# ir.net
KiCad netlist of a schematic drawn in EAGLE
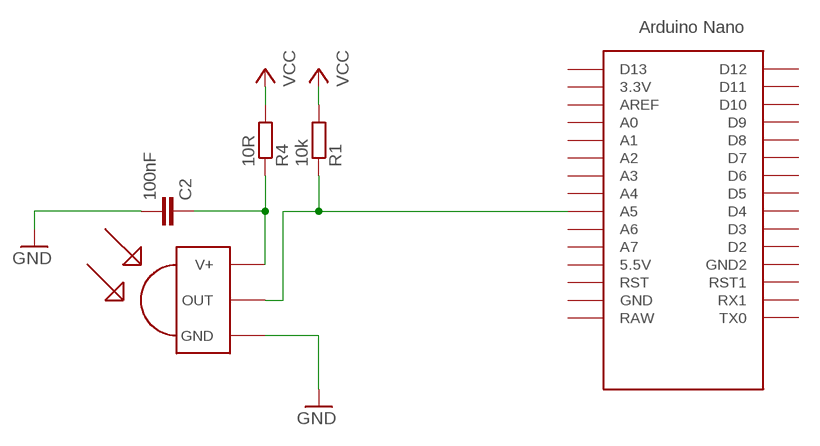
[diagram p0: schematic, sheet 1]

(export (version "E")
  (design (tool "Eeschema 10.0.6"))
  (components
    (comp (ref "C2")
      (value "100nF")
      (footprint "eagle-import:C025-025X050")
      (libsource (lib "eagle-import") (part "C-EU025-025X050"))
    )
    (comp (ref "R1")
      (value "10k")
      (footprint "eagle-import:0207_10")
      (libsource (lib "eagle-import") (part "R-EU_0207/10"))
    )
    (comp (ref "R4")
      (value "10R")
      (footprint "eagle-import:0207_10")
      (libsource (lib "eagle-import") (part "R-EU_0207/10"))
    )
    (comp (ref "U$1")
      (value "TSOP4838")
      (footprint "eagle-import:TSOP18XX")
      (libsource (lib "eagle-import") (part "TSOP4838"))
    )
    (comp (ref "U$2")
      (value "NANO")
      (footprint "eagle-import:NANO")
      (libsource (lib "eagle-import") (part "NANO"))
    )
  )
  (nets
    (net (code "1") (name "GND") (class "Default")
      (node (ref "C2") (pin "2") (pinfunction "2_2") (pintype "passive"))
      (node (ref "U$1") (pin "GND") (pinfunction "GND_GND") (pintype "bidirectional"))
    )
    (net (code "2") (name "Net-(R1-Pad1)") (class "Default")
      (node (ref "R1") (pin "1") (pinfunction "1_1") (pintype "passive"))
      (node (ref "U$1") (pin "OUT") (pinfunction "OUT_OUT") (pintype "bidirectional"))
      (node (ref "U$2") (pin "A5") (pinfunction "A5_A5") (pintype "bidirectional"))
    )
    (net (code "3") (name "Net-(U$1-V+)") (class "Default")
      (node (ref "C2") (pin "1") (pinfunction "1_1") (pintype "passive"))
      (node (ref "R4") (pin "1") (pinfunction "1_1") (pintype "passive"))
      (node (ref "U$1") (pin "VCC") (pinfunction "V+_VCC") (pintype "bidirectional"))
    )
    (net (code "4") (name "VCC") (class "Default")
      (node (ref "R1") (pin "2") (pinfunction "2_2") (pintype "passive"))
      (node (ref "R4") (pin "2") (pinfunction "2_2") (pintype "passive"))
    )
    (net (code "5") (name "unconnected-(U$2-5.5V-Pad5V)") (class "Default")
      (node (ref "U$2") (pin "5V") (pinfunction "5.5V_5V") (pintype "bidirectional"))
    )
    (net (code "6") (name "unconnected-(U$2-GND2-PadGND1)") (class "Default")
      (node (ref "U$2") (pin "GND1") (pinfunction "GND2_GND1") (pintype "bidirectional"))
    )
    (net (code "7") (name "unconnected-(U$2-Pad3.3V)") (class "Default")
      (node (ref "U$2") (pin "3.3V") (pinfunction "3.3V_3.3V") (pintype "bidirectional"))
    )
    (net (code "8") (name "unconnected-(U$2-PadA0)") (class "Default")
      (node (ref "U$2") (pin "A0") (pinfunction "A0_A0") (pintype "bidirectional"))
    )
    (net (code "9") (name "unconnected-(U$2-PadA1)") (class "Default")
      (node (ref "U$2") (pin "A1") (pinfunction "A1_A1") (pintype "bidirectional"))
    )
    (net (code "10") (name "unconnected-(U$2-PadA2)") (class "Default")
      (node (ref "U$2") (pin "A2") (pinfunction "A2_A2") (pintype "bidirectional"))
    )
    (net (code "11") (name "unconnected-(U$2-PadA3)") (class "Default")
      (node (ref "U$2") (pin "A3") (pinfunction "A3_A3") (pintype "bidirectional"))
    )
    (net (code "12") (name "unconnected-(U$2-PadA4)") (class "Default")
      (node (ref "U$2") (pin "A4") (pinfunction "A4_A4") (pintype "bidirectional"))
    )
    (net (code "13") (name "unconnected-(U$2-PadA6)") (class "Default")
      (node (ref "U$2") (pin "A6") (pinfunction "A6_A6") (pintype "bidirectional"))
    )
    (net (code "14") (name "unconnected-(U$2-PadA7)") (class "Default")
      (node (ref "U$2") (pin "A7") (pinfunction "A7_A7") (pintype "bidirectional"))
    )
    (net (code "15") (name "unconnected-(U$2-PadAREF)") (class "Default")
      (node (ref "U$2") (pin "AREF") (pinfunction "AREF_AREF") (pintype "bidirectional"))
    )
    (net (code "16") (name "unconnected-(U$2-PadD2)") (class "Default")
      (node (ref "U$2") (pin "D2") (pinfunction "D2_D2") (pintype "bidirectional"))
    )
    (net (code "17") (name "unconnected-(U$2-PadD3)") (class "Default")
      (node (ref "U$2") (pin "D3") (pinfunction "D3_D3") (pintype "bidirectional"))
    )
    (net (code "18") (name "unconnected-(U$2-PadD4)") (class "Default")
      (node (ref "U$2") (pin "D4") (pinfunction "D4_D4") (pintype "bidirectional"))
    )
    (net (code "19") (name "unconnected-(U$2-PadD5)") (class "Default")
      (node (ref "U$2") (pin "D5") (pinfunction "D5_D5") (pintype "bidirectional"))
    )
    (net (code "20") (name "unconnected-(U$2-PadD6)") (class "Default")
      (node (ref "U$2") (pin "D6") (pinfunction "D6_D6") (pintype "bidirectional"))
    )
    (net (code "21") (name "unconnected-(U$2-PadD7)") (class "Default")
      (node (ref "U$2") (pin "D7") (pinfunction "D7_D7") (pintype "bidirectional"))
    )
    (net (code "22") (name "unconnected-(U$2-PadD8)") (class "Default")
      (node (ref "U$2") (pin "D8") (pinfunction "D8_D8") (pintype "bidirectional"))
    )
    (net (code "23") (name "unconnected-(U$2-PadD9)") (class "Default")
      (node (ref "U$2") (pin "D9") (pinfunction "D9_D9") (pintype "bidirectional"))
    )
    (net (code "24") (name "unconnected-(U$2-PadD10)") (class "Default")
      (node (ref "U$2") (pin "D10") (pinfunction "D10_D10") (pintype "bidirectional"))
    )
    (net (code "25") (name "unconnected-(U$2-PadD11)") (class "Default")
      (node (ref "U$2") (pin "D11") (pinfunction "D11_D11") (pintype "bidirectional"))
    )
    (net (code "26") (name "unconnected-(U$2-PadD12)") (class "Default")
      (node (ref "U$2") (pin "D12") (pinfunction "D12_D12") (pintype "bidirectional"))
    )
    (net (code "27") (name "unconnected-(U$2-PadD13)") (class "Default")
      (node (ref "U$2") (pin "D13") (pinfunction "D13_D13") (pintype "bidirectional"))
    )
    (net (code "28") (name "unconnected-(U$2-PadGND)") (class "Default")
      (node (ref "U$2") (pin "GND") (pinfunction "GND_GND") (pintype "bidirectional"))
    )
    (net (code "29") (name "unconnected-(U$2-PadICSP1)") (class "Default")
      (node (ref "U$2") (pin "ICSP1") (pinfunction "ICSP1_ICSP1") (pintype "bidirectional"))
    )
    (net (code "30") (name "unconnected-(U$2-PadICSP2)") (class "Default")
      (node (ref "U$2") (pin "ICSP2") (pinfunction "ICSP2_ICSP2") (pintype "bidirectional"))
    )
    (net (code "31") (name "unconnected-(U$2-PadICSP3)") (class "Default")
      (node (ref "U$2") (pin "ICSP3") (pinfunction "ICSP3_ICSP3") (pintype "bidirectional"))
    )
    (net (code "32") (name "unconnected-(U$2-PadICSP4)") (class "Default")
      (node (ref "U$2") (pin "ICSP4") (pinfunction "ICSP4_ICSP4") (pintype "bidirectional"))
    )
    (net (code "33") (name "unconnected-(U$2-PadICSP5)") (class "Default")
      (node (ref "U$2") (pin "ICSP5") (pinfunction "ICSP5_ICSP5") (pintype "bidirectional"))
    )
    (net (code "34") (name "unconnected-(U$2-PadICSP6)") (class "Default")
      (node (ref "U$2") (pin "ICSP6") (pinfunction "ICSP6_ICSP6") (pintype "bidirectional"))
    )
    (net (code "35") (name "unconnected-(U$2-PadRAW)") (class "Default")
      (node (ref "U$2") (pin "RAW") (pinfunction "RAW_RAW") (pintype "bidirectional"))
    )
    (net (code "36") (name "unconnected-(U$2-PadRST)") (class "Default")
      (node (ref "U$2") (pin "RST") (pinfunction "RST_RST") (pintype "bidirectional"))
    )
    (net (code "37") (name "unconnected-(U$2-PadRST1)") (class "Default")
      (node (ref "U$2") (pin "RST1") (pinfunction "RST1_RST1") (pintype "bidirectional"))
    )
    (net (code "38") (name "unconnected-(U$2-PadRX1)") (class "Default")
      (node (ref "U$2") (pin "RX1") (pinfunction "RX1_RX1") (pintype "bidirectional"))
    )
    (net (code "39") (name "unconnected-(U$2-PadTX0)") (class "Default")
      (node (ref "U$2") (pin "TX0") (pinfunction "TX0_TX0") (pintype "bidirectional"))
    )
  )
)
